# Power_Supplies.net
KiCad netlist of a schematic drawn in Altium Designer
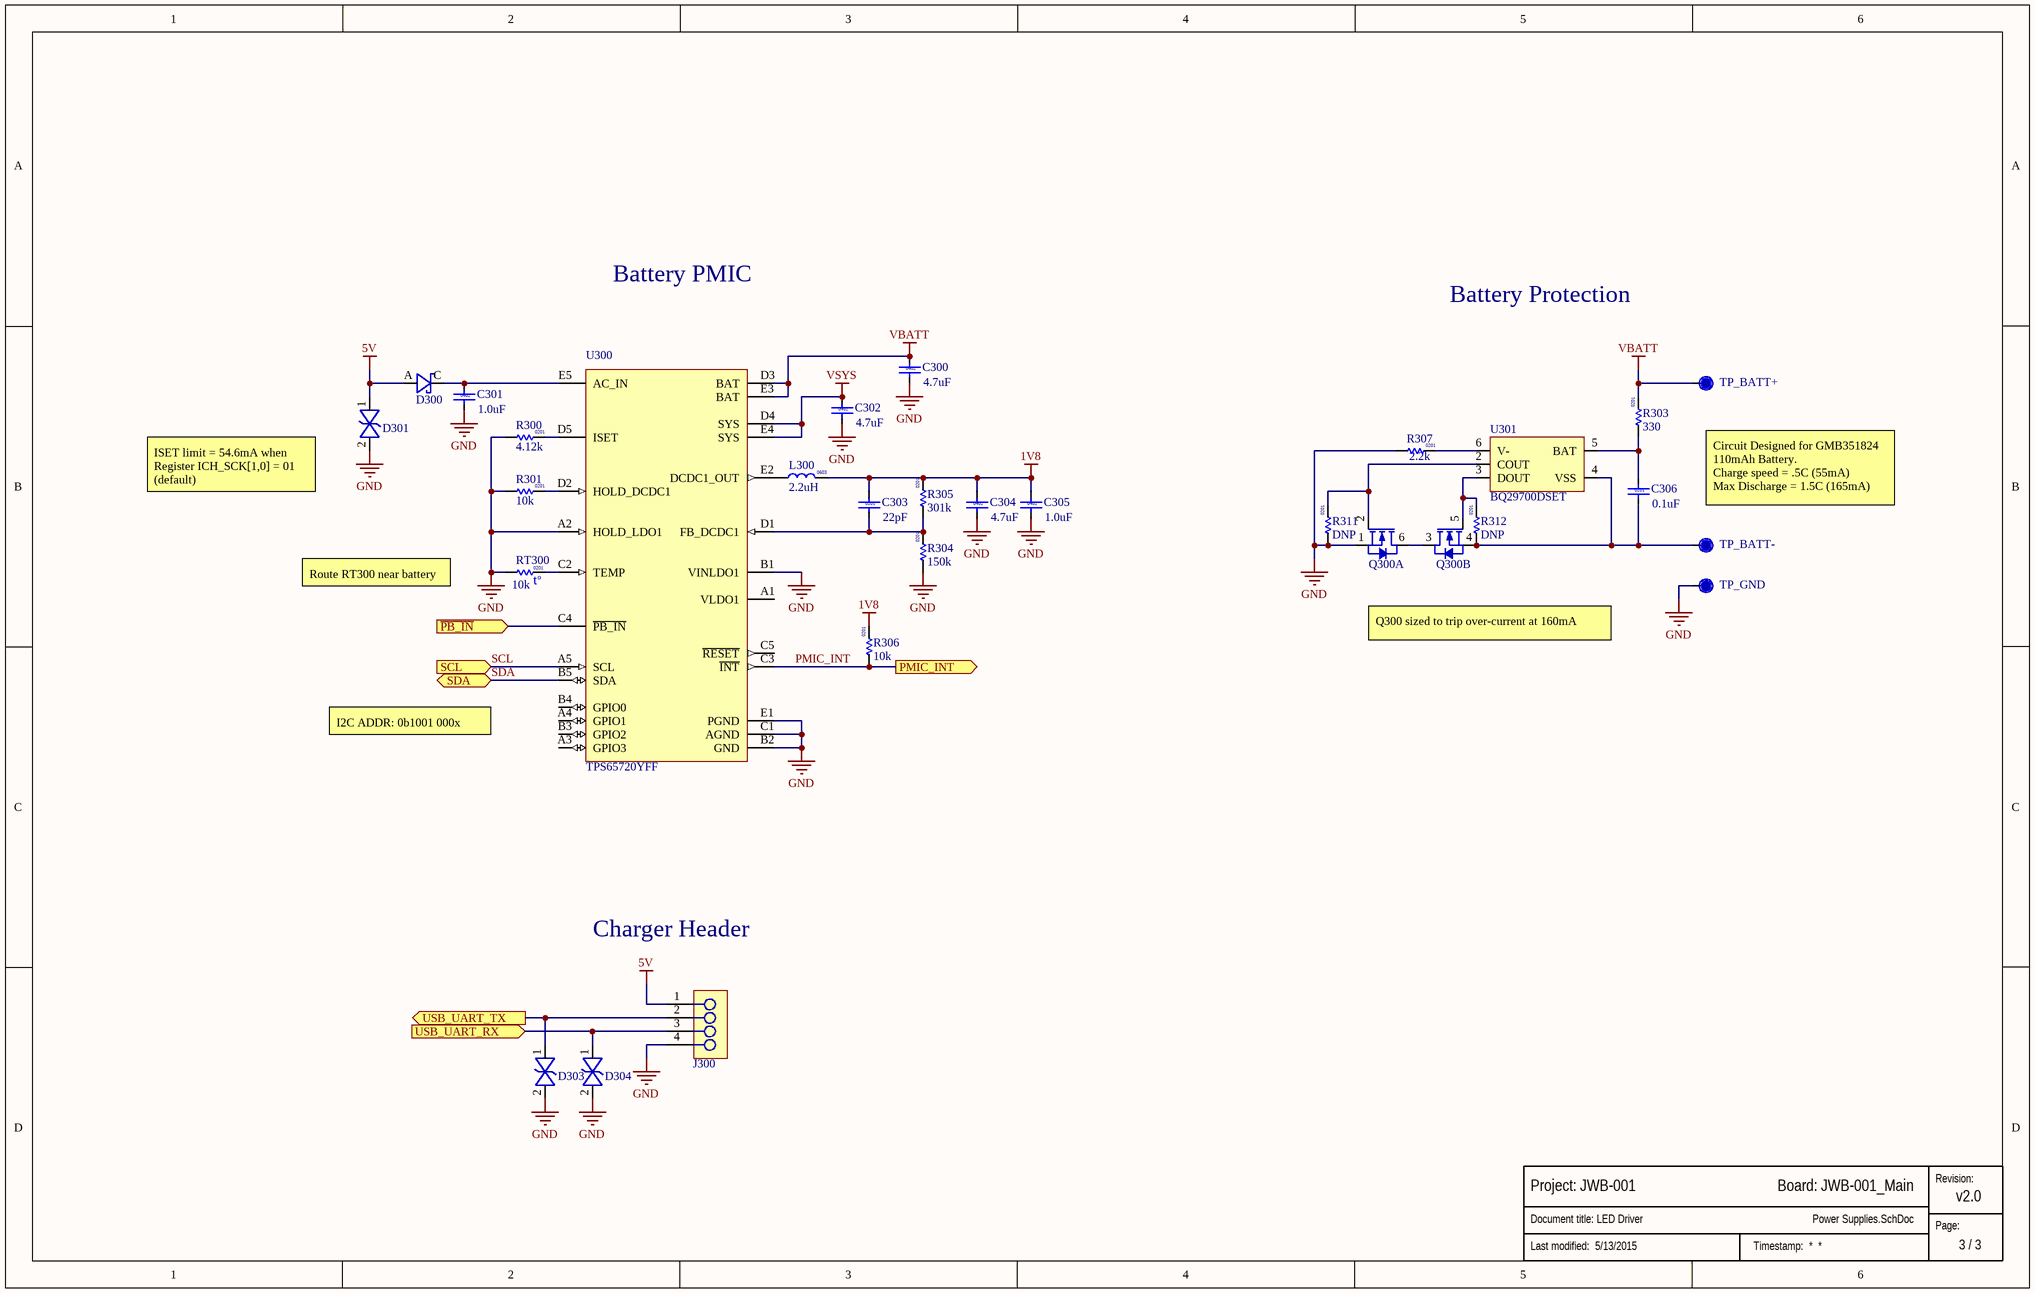
[diagram p0: Power Supplies.SchDoc]

(export (version "E")
  (design (tool "Eeschema 10.0.6"))
  (components
    (comp (ref "C300")
      (value "4.7uF")
      (footprint "Cap 0402 HD")
      (description "Cap, Ceramic 4.7uF 10V 20% X5R 0402")
      (fields
        (field (name "SIZE") "0402")
        (field (name "PART NUMBER") "Cap 0402 4.7uF 10V")
        (field (name "TOLERANCE") "20%")
        (field (name "ADDED BY") "Jeremy D")
        (field (name "CHECKED BY") "Paul B")
      )
      (libsource (lib "Rigado_AltiumLib") (part "Cap Chip"))
    )
    (comp (ref "C301")
      (value "1.0uF")
      (footprint "Cap 0402 HD")
      (description "Cap, Ceramic 1.0uF 10V 10% X5R 0402")
      (fields
        (field (name "SIZE") "0402")
        (field (name "PART NUMBER") "Cap 0402 1.0uF 10V")
        (field (name "TOLERANCE") "10%")
        (field (name "ADDED BY") "Jeremy D")
        (field (name "CHECKED BY") "Paul B")
      )
      (libsource (lib "Rigado_AltiumLib") (part "Cap Chip"))
    )
    (comp (ref "C302")
      (value "4.7uF")
      (footprint "Cap 0402 HD")
      (description "Cap, Ceramic 4.7uF 10V 20% X5R 0402")
      (fields
        (field (name "SIZE") "0402")
        (field (name "PART NUMBER") "Cap 0402 4.7uF 10V")
        (field (name "TOLERANCE") "20%")
        (field (name "ADDED BY") "Jeremy D")
        (field (name "CHECKED BY") "Paul B")
      )
      (libsource (lib "Rigado_AltiumLib") (part "Cap Chip"))
    )
    (comp (ref "C303")
      (value "22pF")
      (footprint "Cap 0201 HD")
      (description "Cap, Ceramic 22pF 50V 5% NPO  0201")
      (fields
        (field (name "SIZE") "0201")
        (field (name "PART NUMBER") "Cap 0201 22pF 50V")
        (field (name "TOLERANCE") "5%")
        (field (name "ADDED BY") "Jeremy D")
        (field (name "CHECKED BY") "Cam N")
      )
      (libsource (lib "Rigado_AltiumLib") (part "Cap Chip"))
    )
    (comp (ref "C304")
      (value "4.7uF")
      (footprint "Cap 0402 HD")
      (description "Cap, Ceramic 4.7uF 10V 20% X5R 0402")
      (fields
        (field (name "SIZE") "0402")
        (field (name "PART NUMBER") "Cap 0402 4.7uF 10V")
        (field (name "TOLERANCE") "20%")
        (field (name "ADDED BY") "Jeremy D")
        (field (name "CHECKED BY") "Paul B")
      )
      (libsource (lib "Rigado_AltiumLib") (part "Cap Chip"))
    )
    (comp (ref "C305")
      (value "1.0uF")
      (footprint "Cap 0402 HD")
      (description "Cap, Ceramic 1.0uF 10V 10% X5R 0402")
      (fields
        (field (name "SIZE") "0402")
        (field (name "PART NUMBER") "Cap 0402 1.0uF 10V")
        (field (name "TOLERANCE") "10%")
        (field (name "ADDED BY") "Jeremy D")
        (field (name "CHECKED BY") "Paul B")
      )
      (libsource (lib "Rigado_AltiumLib") (part "Cap Chip"))
    )
    (comp (ref "C306")
      (value "0.1uF")
      (footprint "Cap 0201 HD")
      (description "Cap, Ceramic 0.1uF 6.3V 10% X5R  0201")
      (fields
        (field (name "SIZE") "0201")
        (field (name "PART NUMBER") "Cap 0201 0.1uF 6.3V")
        (field (name "TOLERANCE") "10%")
        (field (name "ADDED BY") "Jeremy D")
        (field (name "CHECKED BY") "Cam N")
      )
      (libsource (lib "Rigado_AltiumLib") (part "Cap Chip"))
    )
    (comp (ref "D300")
      (value "CDBU05x020V")
      (footprint "Diode 0603 HD")
      (description "Diode, Schottky, 20V 500mA, 470mV Vf @ 500mA, 0603")
      (fields
        (field (name "PART NUMBER") "CDBU05x0")
        (field (name "MANUFACTURER") "Comchip Technology")
        (field (name "ADDED BY") "Jeremy D")
      )
      (libsource (lib "LOCAL_Rigado_AltiumLib") (part "Diode_Schottky"))
    )
    (comp (ref "D301")
      (value "SESD0402P1BN-0450-0906V")
      (footprint "CAP 0402 HD")
      (description "ESD TVS Diode, 16kV air, 0402")
      (fields
        (field (name "PART NUMBER") "SESD0402P1BN-0450-090")
        (field (name "MANUFACTURER") "TE Connectivity")
        (field (name "ADDED BY") "Jeremy D")
        (field (name "CHECKED BY") "Paul B")
      )
      (libsource (lib "Rigado_AltiumLib") (part "Diode_TVS"))
    )
    (comp (ref "D303")
      (value "SESD0402P1BN-0450-0906V")
      (footprint "CAP 0402 HD")
      (description "ESD TVS Diode, 16kV air, 0402")
      (fields
        (field (name "PART NUMBER") "SESD0402P1BN-0450-090")
        (field (name "MANUFACTURER") "TE Connectivity")
        (field (name "ADDED BY") "Jeremy D")
        (field (name "CHECKED BY") "Paul B")
      )
      (libsource (lib "Rigado_AltiumLib") (part "Diode_TVS"))
    )
    (comp (ref "D304")
      (value "SESD0402P1BN-0450-0906V")
      (footprint "CAP 0402 HD")
      (description "ESD TVS Diode, 16kV air, 0402")
      (fields
        (field (name "PART NUMBER") "SESD0402P1BN-0450-090")
        (field (name "MANUFACTURER") "TE Connectivity")
        (field (name "ADDED BY") "Jeremy D")
        (field (name "CHECKED BY") "Paul B")
      )
      (libsource (lib "Rigado_AltiumLib") (part "Diode_TVS"))
    )
    (comp (ref "J300")
      (value "854-22-004-30-001101")
      (footprint "HDR.050P-4Pin-SMT-R")
      (description "Spring Loaded Header 0.05\" Pitch, 4Pin, 4x1, 4.98mm - 6.4mm Height")
      (fields
        (field (name "MANUFACTURER") "Mill-Max")
        (field (name "ADDED BY") "Jeremy D")
        (field (name "CHECKED BY") "Cam N")
      )
      (libsource (lib "Rigado_AltiumLib") (part "CON-4Pin_1Row"))
    )
    (comp (ref "L300")
      (value "2.2uH")
      (footprint "IND 0603")
      (description "Inductor, 2.2uH 160mA, 0603")
      (fields
        (field (name "SIZE") "0603")
        (field (name "PART NUMBER") "Ind 0603 2.2uH 160mA")
        (field (name "MANUFACTURER") "TDK")
        (field (name "ADDED BY") "Jeremy D")
        (field (name "CHECKED BY") "Cam N")
      )
      (libsource (lib "Rigado_AltiumLib") (part "Ind sm"))
    )
    (comp (ref "Q300")
      (value "Si1902CDL")
      (footprint "SC70-6")
      (description "Dual N-MOSFET, 20V 1A, SC70-6")
      (fields
        (field (name "MANUFACTURER") "Vishay")
        (field (name "ADDED BY") "Jeremy D")
        (field (name "CHECKED BY") "Cam N")
      )
      (libsource (lib "LOCAL_Rigado_AltiumLib") (part "MOSFET-N-Dual"))
    )
    (comp (ref "R300")
      (value "4.12k")
      (footprint "RES 0201 HD")
      (description "RES SMD 4.12K OHM 1% 1/20W 0201")
      (fields
        (field (name "SIZE") "0201")
        (field (name "PART NUMBER") "Res 0201 Generic")
        (field (name "MANUFACTURER") "Panasonic")
        (field (name "ADDED BY") "Jeremy D")
        (field (name "CHECKED BY") "Paul B")
      )
      (libsource (lib "Rigado_AltiumLib") (part "Res sm"))
    )
    (comp (ref "R301")
      (value "10k")
      (footprint "RES 0201 HD")
      (description "Resistor 10k ohm 5% 1/20W 0201")
      (fields
        (field (name "SIZE") "0201")
        (field (name "PART NUMBER") "Res 0201 10k 5%")
        (field (name "MANUFACTURER") "Rohm")
        (field (name "ADDED BY") "Jeremy D")
        (field (name "CHECKED BY") "Paul B")
      )
      (libsource (lib "Rigado_AltiumLib") (part "Res sm"))
    )
    (comp (ref "R303")
      (value "330")
      (footprint "RES 0201 HD")
      (description "Resistor 330 ohm 5% 1/20W, 0201")
      (fields
        (field (name "SIZE") "0201")
        (field (name "PART NUMBER") "Res 0201 330R 5%")
        (field (name "MANUFACTURER") "Rohm")
        (field (name "ADDED BY") "Jeremy D")
        (field (name "CHECKED BY") "Cam N")
      )
      (libsource (lib "Rigado_AltiumLib") (part "Res sm"))
    )
    (comp (ref "R304")
      (value "150k")
      (footprint "RES 0201 HD")
      (description "Resistor 150k ohm  1% 1/20W, 0201")
      (fields
        (field (name "SIZE") "0201")
        (field (name "PART NUMBER") "Res 0201 150k 1%")
        (field (name "MANUFACTURER") "Rohm")
        (field (name "ADDED BY") "Jeremy D")
        (field (name "CHECKED BY") "Cam N")
      )
      (libsource (lib "Rigado_AltiumLib") (part "Res sm"))
    )
    (comp (ref "R305")
      (value "301k")
      (footprint "RES 0201 HD")
      (description "Resistor 301k ohm 1% 1/20W, 0201")
      (fields
        (field (name "SIZE") "0201")
        (field (name "PART NUMBER") "Res 0201 301k 1%")
        (field (name "MANUFACTURER") "Panasonic")
        (field (name "ADDED BY") "Jeremy D")
      )
      (libsource (lib "LOCAL_Rigado_AltiumLib") (part "Res sm"))
    )
    (comp (ref "R306")
      (value "10k")
      (footprint "RES 0201 HD")
      (description "Resistor 10k ohm 5% 1/20W 0201")
      (fields
        (field (name "SIZE") "0201")
        (field (name "PART NUMBER") "Res 0201 10k 5%")
        (field (name "MANUFACTURER") "Rohm")
        (field (name "ADDED BY") "Jeremy D")
        (field (name "CHECKED BY") "Paul B")
      )
      (libsource (lib "Rigado_AltiumLib") (part "Res sm"))
    )
    (comp (ref "R307")
      (value "2.2k")
      (footprint "RES 0201 HD")
      (description "Resistor 2.2k ohm 5% 1/20W, 0201")
      (fields
        (field (name "SIZE") "0201")
        (field (name "PART NUMBER") "Res 0201 2.2k 5%")
        (field (name "MANUFACTURER") "Panasonic")
        (field (name "ADDED BY") "Jeremy D")
        (field (name "CHECKED BY") "Cam N")
      )
      (libsource (lib "Rigado_AltiumLib") (part "Res sm"))
    )
    (comp (ref "R311")
      (value "DNP")
      (footprint "RES 0201 HD")
      (description "Resistor, 0201")
      (fields
        (field (name "SIZE") "0201")
        (field (name "PART NUMBER") "Res 0201 Generic")
        (field (name "Comment") "Res 0201 GenericDNPDNP")
        (field (name "ADDED BY") "Jeremy D")
        (field (name "CHECKED BY") "Paul B")
      )
      (libsource (lib "Rigado_AltiumLib") (part "Res sm"))
    )
    (comp (ref "R312")
      (value "DNP")
      (footprint "RES 0201 HD")
      (description "Resistor, 0201")
      (fields
        (field (name "SIZE") "0201")
        (field (name "PART NUMBER") "Res 0201 Generic")
        (field (name "Comment") "Res 0201 GenericDNPDNP")
        (field (name "ADDED BY") "Jeremy D")
        (field (name "CHECKED BY") "Paul B")
      )
      (libsource (lib "Rigado_AltiumLib") (part "Res sm"))
    )
    (comp (ref "RT300")
      (value "10k")
      (footprint "RES 0201 HD")
      (description "Thermistor 10k ohm NTC 5% 0201")
      (fields
        (field (name "SIZE") "0201")
        (field (name "PART NUMBER") "Therm 0201 10k NTC")
        (field (name "MANUFACTURER") "Murata")
        (field (name "ADDED BY") "Jeremy D")
        (field (name "CHECKED BY") "Cam N")
      )
      (libsource (lib "Rigado_AltiumLib") (part "Res Thermal"))
    )
    (comp (ref "TP_BATT+")
      (value "TP")
      (footprint "TP17R")
      (description "Testpoint, Round 1.7mm Dia")
      (fields
        (field (name "PART NUMBER") "TP17R")
        (field (name "ADDED BY") "Jeremy D")
        (field (name "CHECKED BY") "Paul B")
      )
      (libsource (lib "Rigado_AltiumLib") (part "TP_R"))
    )
    (comp (ref "TP_BATT-")
      (value "TP")
      (footprint "TP17R")
      (description "Testpoint, Round 1.7mm Dia")
      (fields
        (field (name "PART NUMBER") "TP17R")
        (field (name "ADDED BY") "Jeremy D")
        (field (name "CHECKED BY") "Paul B")
      )
      (libsource (lib "Rigado_AltiumLib") (part "TP_R"))
    )
    (comp (ref "TP_GND")
      (value "TP")
      (footprint "TP17R")
      (description "Testpoint, Round 1.7mm Dia")
      (fields
        (field (name "PART NUMBER") "TP17R")
        (field (name "ADDED BY") "Jeremy D")
        (field (name "CHECKED BY") "Paul B")
      )
      (libsource (lib "Rigado_AltiumLib") (part "TP_R"))
    )
    (comp (ref "U300")
      (value "TPS65720")
      (footprint "BGA0.4P5x5-25Pin")
      (description "PMU for Li-ion batteries, 1xDCDC 1xLDO, .4mm pitch XBGA 2mm x 2mm")
      (fields
        (field (name "MANUFACTURER P/N") "TPS65720YFF")
        (field (name "MANUFACTURER") "Texas Instruments")
        (field (name "ADDED BY") "Jeremy D")
      )
      (libsource (lib "LOCAL_Rigado_AltiumLib") (part "TPS65720"))
    )
    (comp (ref "U301")
      (value "BQ29700")
      (footprint "SON0.5P-6Pin")
      (description "Li-Ion single cell voltage and current protection IC")
      (fields
        (field (name "MANUFACTURER P/N") "BQ29700DSET")
        (field (name "MANUFACTURER") "Texas Instruments")
        (field (name "ADDED BY") "Jeremy D")
        (field (name "CHECKED BY") "Cam N")
      )
      (libsource (lib "Rigado_AltiumLib") (part "BQ2970x"))
    )
  )
  (nets
    (net (code "1") (name "/PB_IN") (class "Default")
      (node (ref "U300") (pin "C4") (pinfunction "PB_IN_C4") (pintype "passive"))
    )
    (net (code "2") (name "/PMIC_INT") (class "Default")
      (node (ref "R306") (pin "1") (pinfunction "1_1") (pintype "passive"))
      (node (ref "U300") (pin "C3") (pinfunction "INT_C3") (pintype "output"))
    )
    (net (code "3") (name "/SCL") (class "Default")
      (node (ref "U300") (pin "A5") (pinfunction "SCL_A5") (pintype "input"))
    )
    (net (code "4") (name "/SDA") (class "Default")
      (node (ref "U300") (pin "B5") (pinfunction "SDA_B5") (pintype "bidirectional"))
    )
    (net (code "5") (name "/USB_UART_RX") (class "Default")
      (node (ref "D304") (pin "1") (pintype "passive"))
      (node (ref "J300") (pin "3") (pinfunction "3_3") (pintype "passive"))
    )
    (net (code "6") (name "/USB_UART_TX") (class "Default")
      (node (ref "D303") (pin "1") (pintype "passive"))
      (node (ref "J300") (pin "2") (pinfunction "2_2") (pintype "passive"))
    )
    (net (code "7") (name "1V8") (class "Default")
      (node (ref "C303") (pin "1") (pinfunction "1_1") (pintype "passive"))
      (node (ref "C304") (pin "1") (pinfunction "1_1") (pintype "passive"))
      (node (ref "C305") (pin "1") (pinfunction "1_1") (pintype "passive"))
      (node (ref "L300") (pin "2") (pinfunction "2_2") (pintype "passive"))
      (node (ref "R305") (pin "2") (pinfunction "2_2") (pintype "passive"))
      (node (ref "R306") (pin "2") (pinfunction "2_2") (pintype "passive"))
    )
    (net (code "8") (name "5V") (class "Default")
      (node (ref "D300") (pin "A") (pintype "passive"))
      (node (ref "D301") (pin "1") (pintype "passive"))
      (node (ref "J300") (pin "1") (pinfunction "1_1") (pintype "passive"))
    )
    (net (code "9") (name "GND") (class "Default")
      (node (ref "C300") (pin "2") (pinfunction "2_2") (pintype "passive"))
      (node (ref "C301") (pin "2") (pinfunction "2_2") (pintype "passive"))
      (node (ref "C302") (pin "2") (pinfunction "2_2") (pintype "passive"))
      (node (ref "C304") (pin "2") (pinfunction "2_2") (pintype "passive"))
      (node (ref "C305") (pin "2") (pinfunction "2_2") (pintype "passive"))
      (node (ref "D301") (pin "2") (pintype "passive"))
      (node (ref "D303") (pin "2") (pintype "passive"))
      (node (ref "D304") (pin "2") (pintype "passive"))
      (node (ref "J300") (pin "4") (pinfunction "4_4") (pintype "passive"))
      (node (ref "Q300") (pin "1") (pinfunction "S1_1") (pintype "passive"))
      (node (ref "R300") (pin "1") (pinfunction "1_1") (pintype "passive"))
      (node (ref "R301") (pin "1") (pinfunction "1_1") (pintype "passive"))
      (node (ref "R304") (pin "1") (pinfunction "1_1") (pintype "passive"))
      (node (ref "R307") (pin "1") (pinfunction "1_1") (pintype "passive"))
      (node (ref "R311") (pin "1") (pinfunction "1_1") (pintype "passive"))
      (node (ref "RT300") (pin "2") (pinfunction "2_2") (pintype "passive"))
      (node (ref "TP_GND") (pin "1") (pintype "passive"))
      (node (ref "U300") (pin "A2") (pinfunction "HOLD_LDO1_A2") (pintype "input"))
      (node (ref "U300") (pin "B1") (pinfunction "VINLDO1_B1") (pintype "power_in"))
      (node (ref "U300") (pin "B2") (pinfunction "GND_B2") (pintype "power_in"))
      (node (ref "U300") (pin "C1") (pinfunction "AGND_C1") (pintype "power_in"))
      (node (ref "U300") (pin "E1") (pinfunction "PGND_E1") (pintype "power_in"))
    )
    (net (code "10") (name "Net-(Q300A-D1)") (class "Default")
      (node (ref "Q300") (pin "3") (pinfunction "D2_3") (pintype "passive"))
      (node (ref "Q300") (pin "6") (pinfunction "D1_6") (pintype "passive"))
    )
    (net (code "11") (name "Net-(Q300A-G1)") (class "Default")
      (node (ref "Q300") (pin "2") (pinfunction "G1_2") (pintype "passive"))
      (node (ref "R311") (pin "2") (pinfunction "2_2") (pintype "passive"))
      (node (ref "U301") (pin "2") (pinfunction "COUT_2") (pintype "passive"))
    )
    (net (code "12") (name "Net-(Q300B-G2)") (class "Default")
      (node (ref "Q300") (pin "5") (pinfunction "G2_5") (pintype "passive"))
      (node (ref "R312") (pin "2") (pinfunction "2_2") (pintype "passive"))
      (node (ref "U301") (pin "3") (pinfunction "DOUT_3") (pintype "passive"))
    )
    (net (code "13") (name "Net-(Q300B-S2)") (class "Default")
      (node (ref "C306") (pin "2") (pinfunction "2_2") (pintype "passive"))
      (node (ref "Q300") (pin "4") (pinfunction "S2_4") (pintype "passive"))
      (node (ref "R312") (pin "1") (pinfunction "1_1") (pintype "passive"))
      (node (ref "TP_BATT-") (pin "1") (pintype "passive"))
      (node (ref "U301") (pin "4") (pinfunction "VSS_4") (pintype "passive"))
    )
    (net (code "14") (name "Net-(U300-AC_IN)") (class "Default")
      (node (ref "C301") (pin "1") (pinfunction "1_1") (pintype "passive"))
      (node (ref "D300") (pin "C") (pintype "passive"))
      (node (ref "U300") (pin "E5") (pinfunction "AC_IN_E5") (pintype "power_in"))
    )
    (net (code "15") (name "Net-(U300-DCDC1_OUT)") (class "Default")
      (node (ref "L300") (pin "1") (pinfunction "1_1") (pintype "passive"))
      (node (ref "U300") (pin "E2") (pinfunction "DCDC1_OUT_E2") (pintype "output"))
    )
    (net (code "16") (name "Net-(U300-FB_DCDC1)") (class "Default")
      (node (ref "C303") (pin "2") (pinfunction "2_2") (pintype "passive"))
      (node (ref "R304") (pin "2") (pinfunction "2_2") (pintype "passive"))
      (node (ref "R305") (pin "1") (pinfunction "1_1") (pintype "passive"))
      (node (ref "U300") (pin "D1") (pinfunction "FB_DCDC1_D1") (pintype "input"))
    )
    (net (code "17") (name "Net-(U300-HOLD_DCDC1)") (class "Default")
      (node (ref "R301") (pin "2") (pinfunction "2_2") (pintype "passive"))
      (node (ref "U300") (pin "D2") (pinfunction "HOLD_DCDC1_D2") (pintype "input"))
    )
    (net (code "18") (name "Net-(U300-ISET)") (class "Default")
      (node (ref "R300") (pin "2") (pinfunction "2_2") (pintype "passive"))
      (node (ref "U300") (pin "D5") (pinfunction "ISET_D5") (pintype "passive"))
    )
    (net (code "19") (name "Net-(U300-TEMP)") (class "Default")
      (node (ref "RT300") (pin "1") (pinfunction "1_1") (pintype "passive"))
      (node (ref "U300") (pin "C2") (pinfunction "TEMP_C2") (pintype "input"))
    )
    (net (code "20") (name "Net-(U301-BAT)") (class "Default")
      (node (ref "C306") (pin "1") (pinfunction "1_1") (pintype "passive"))
      (node (ref "R303") (pin "1") (pinfunction "1_1") (pintype "passive"))
      (node (ref "U301") (pin "5") (pinfunction "BAT_5") (pintype "passive"))
    )
    (net (code "21") (name "Net-(U301-V-)") (class "Default")
      (node (ref "R307") (pin "2") (pinfunction "2_2") (pintype "passive"))
      (node (ref "U301") (pin "6") (pinfunction "V-_6") (pintype "passive"))
    )
    (net (code "22") (name "VBATT") (class "Default")
      (node (ref "C300") (pin "1") (pinfunction "1_1") (pintype "passive"))
      (node (ref "R303") (pin "2") (pinfunction "2_2") (pintype "passive"))
      (node (ref "TP_BATT+") (pin "1") (pintype "passive"))
      (node (ref "U300") (pin "D3") (pinfunction "BAT_D3") (pintype "power_in"))
      (node (ref "U300") (pin "E3") (pinfunction "BAT_E3") (pintype "power_in"))
    )
    (net (code "23") (name "VSYS") (class "Default")
      (node (ref "C302") (pin "1") (pinfunction "1_1") (pintype "passive"))
      (node (ref "U300") (pin "D4") (pinfunction "SYS_D4") (pintype "power_in"))
      (node (ref "U300") (pin "E4") (pinfunction "SYS_E4") (pintype "power_in"))
    )
    (net (code "24") (name "unconnected-(U300-GPIO0-PadB4)") (class "Default")
      (node (ref "U300") (pin "B4") (pinfunction "GPIO0_B4") (pintype "bidirectional"))
    )
    (net (code "25") (name "unconnected-(U300-GPIO1-PadA4)") (class "Default")
      (node (ref "U300") (pin "A4") (pinfunction "GPIO1_A4") (pintype "bidirectional"))
    )
    (net (code "26") (name "unconnected-(U300-GPIO2-PadB3)") (class "Default")
      (node (ref "U300") (pin "B3") (pinfunction "GPIO2_B3") (pintype "bidirectional"))
    )
    (net (code "27") (name "unconnected-(U300-GPIO3-PadA3)") (class "Default")
      (node (ref "U300") (pin "A3") (pinfunction "GPIO3_A3") (pintype "bidirectional"))
    )
    (net (code "28") (name "unconnected-(U300-RESET-PadC5)") (class "Default")
      (node (ref "U300") (pin "C5") (pinfunction "RESET_C5") (pintype "output"))
    )
    (net (code "29") (name "unconnected-(U300-VLDO1-PadA1)") (class "Default")
      (node (ref "U300") (pin "A1") (pinfunction "VLDO1_A1") (pintype "power_in"))
    )
    (net (code "30") (name "unconnected-(U301-NC-Pad1)") (class "Default")
      (node (ref "U301") (pin "1") (pinfunction "NC_1") (pintype "passive"))
    )
  )
)
